# ORPExpansion.net
KiCad netlist of a schematic drawn in EAGLE
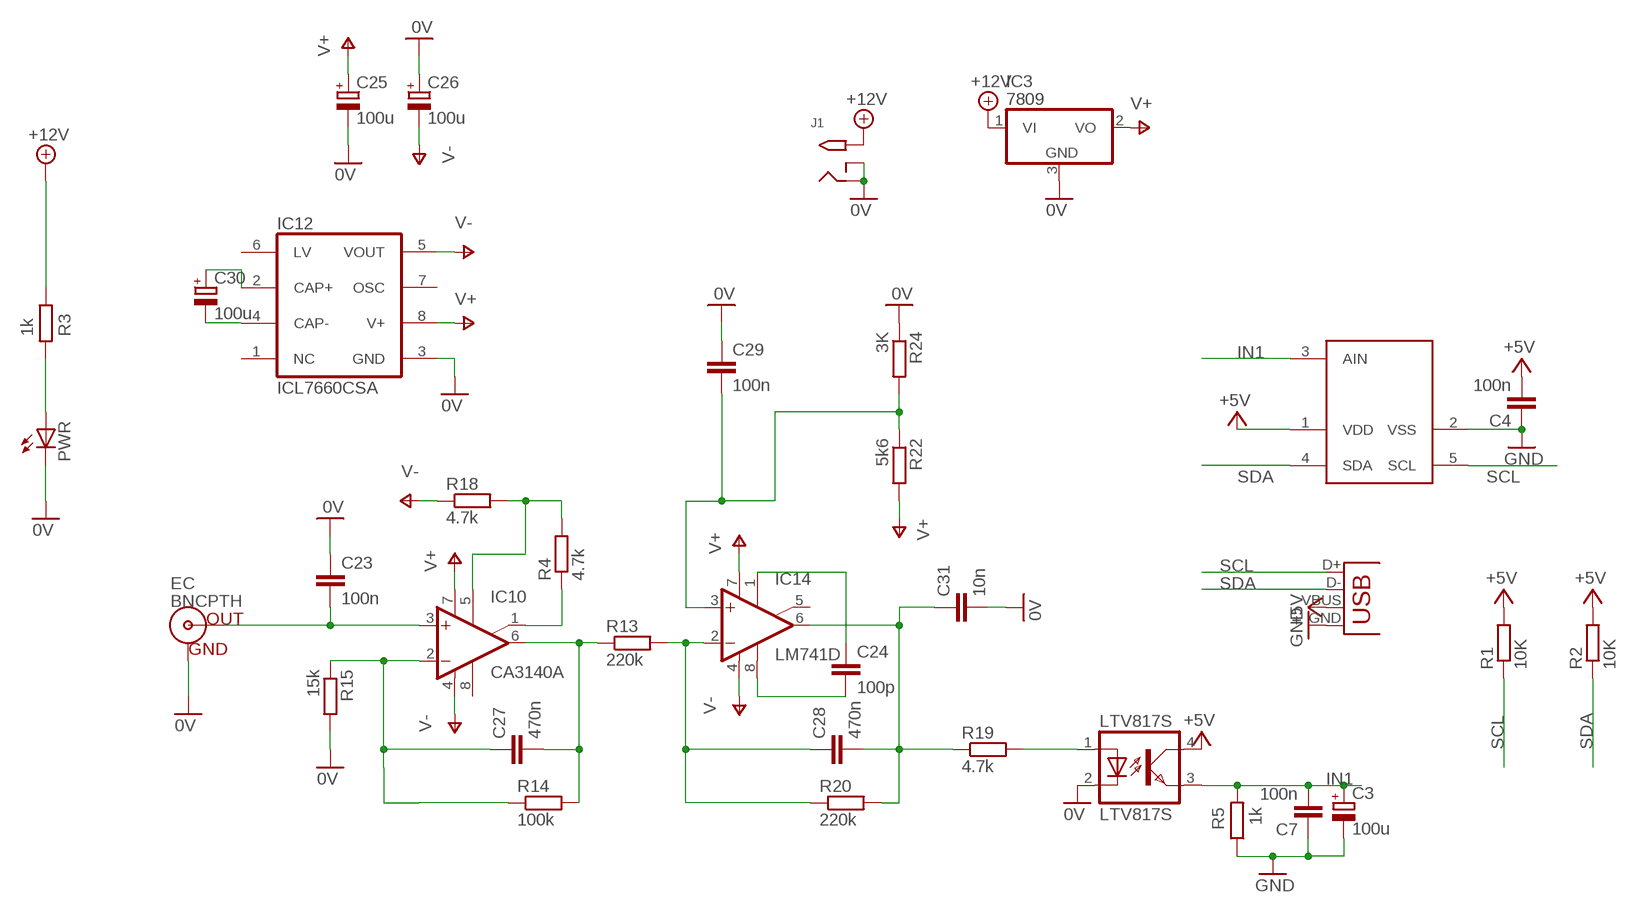
[diagram p0: schematic, sheet 1]

(export (version "E")
  (design (tool "Eeschema 10.0.6"))
  (components
    (comp (ref "C3")
      (value "100u")
      (footprint "eagle-import:PANASONIC_D")
      (libsource (lib "eagle-import") (part "CPOL-EUD"))
    )
    (comp (ref "C4")
      (value "100n")
      (footprint "eagle-import:C0805K")
      (libsource (lib "eagle-import") (part "C-EUC0805K"))
    )
    (comp (ref "C7")
      (value "100n")
      (footprint "eagle-import:C0805K")
      (libsource (lib "eagle-import") (part "C-EUC0805K"))
    )
    (comp (ref "C23")
      (value "100n")
      (footprint "eagle-import:C0805")
      (libsource (lib "eagle-import") (part "C-EUC0805"))
    )
    (comp (ref "C24")
      (value "100p")
      (footprint "eagle-import:C0805")
      (libsource (lib "eagle-import") (part "C-EUC0805"))
    )
    (comp (ref "C25")
      (value "100u")
      (footprint "eagle-import:PANASONIC_D")
      (libsource (lib "eagle-import") (part "CPOL-EUD"))
    )
    (comp (ref "C26")
      (value "100u")
      (footprint "eagle-import:PANASONIC_D")
      (libsource (lib "eagle-import") (part "CPOL-EUD"))
    )
    (comp (ref "C27")
      (value "470n")
      (footprint "eagle-import:C0805")
      (libsource (lib "eagle-import") (part "C-EUC0805"))
    )
    (comp (ref "C28")
      (value "470n")
      (footprint "eagle-import:C0805")
      (libsource (lib "eagle-import") (part "C-EUC0805"))
    )
    (comp (ref "C29")
      (value "100n")
      (footprint "eagle-import:C0805")
      (libsource (lib "eagle-import") (part "C-EUC0805"))
    )
    (comp (ref "C30")
      (value "100u")
      (footprint "eagle-import:PANASONIC_D")
      (libsource (lib "eagle-import") (part "CPOL-EUD"))
    )
    (comp (ref "C31")
      (value "10n")
      (footprint "eagle-import:C0805")
      (libsource (lib "eagle-import") (part "C-EUC0805"))
    )
    (comp (ref "EC")
      (value "BNCPTH")
      (footprint "eagle-import:BNC")
      (libsource (lib "eagle-import") (part "BNCPTH"))
    )
    (comp (ref "IC3")
      (value "7809")
      (footprint "eagle-import:TO252")
      (libsource (lib "eagle-import") (part "78DT05"))
    )
    (comp (ref "IC10")
      (value "CA3140A")
      (footprint "eagle-import:SO08")
      (libsource (lib "eagle-import") (part "CA3140D"))
    )
    (comp (ref "IC12")
      (value "ICL7660CSA")
      (footprint "eagle-import:SO08")
      (libsource (lib "eagle-import") (part "ICL7660CSA"))
    )
    (comp (ref "IC14")
      (value "LM741D")
      (footprint "eagle-import:SO08")
      (libsource (lib "eagle-import") (part "741DLM"))
    )
    (comp (ref "J1")
      (value "2.1MMJACKTHM")
      (footprint "eagle-import:PJ-102A")
      (libsource (lib "eagle-import") (part "2.1MMJACKTHM"))
    )
    (comp (ref "LTV817S")
      (value "LTV817S")
      (footprint "eagle-import:SMD4")
      (libsource (lib "eagle-import") (part "LTV816S"))
    )
    (comp (ref "PWR")
      (value "LED3MM")
      (footprint "eagle-import:LED3MM")
      (libsource (lib "eagle-import") (part "LED3MM"))
    )
    (comp (ref "R1")
      (value "10K")
      (footprint "eagle-import:R0805")
      (libsource (lib "eagle-import") (part "R-EU_R0805"))
    )
    (comp (ref "R2")
      (value "10K")
      (footprint "eagle-import:R0805")
      (libsource (lib "eagle-import") (part "R-EU_R0805"))
    )
    (comp (ref "R3")
      (value "1k")
      (footprint "eagle-import:R0805")
      (libsource (lib "eagle-import") (part "R-EU_R0805"))
    )
    (comp (ref "R4")
      (value "4.7k")
      (footprint "eagle-import:R0805")
      (libsource (lib "eagle-import") (part "R-EU_R0805"))
    )
    (comp (ref "R5")
      (value "1k")
      (footprint "eagle-import:R0805")
      (libsource (lib "eagle-import") (part "R-EU_R0805"))
    )
    (comp (ref "R13")
      (value "220k")
      (footprint "eagle-import:R0805")
      (libsource (lib "eagle-import") (part "R-EU_R0805"))
    )
    (comp (ref "R14")
      (value "100k")
      (footprint "eagle-import:R0805")
      (libsource (lib "eagle-import") (part "R-EU_R0805"))
    )
    (comp (ref "R15")
      (value "15k")
      (footprint "eagle-import:R0805")
      (libsource (lib "eagle-import") (part "R-EU_R0805"))
    )
    (comp (ref "R18")
      (value "4.7k")
      (footprint "eagle-import:R0805")
      (libsource (lib "eagle-import") (part "R-EU_R0805"))
    )
    (comp (ref "R19")
      (value "4.7k")
      (footprint "eagle-import:R0805")
      (libsource (lib "eagle-import") (part "R-EU_R0805"))
    )
    (comp (ref "R20")
      (value "220k")
      (footprint "eagle-import:R0805")
      (libsource (lib "eagle-import") (part "R-EU_R0805"))
    )
    (comp (ref "R22")
      (value "5k6")
      (footprint "eagle-import:R0805")
      (libsource (lib "eagle-import") (part "R-EU_R0805"))
    )
    (comp (ref "R24")
      (value "3K")
      (footprint "eagle-import:R0805")
      (libsource (lib "eagle-import") (part "R-EU_R0805"))
    )
    (comp (ref "U$2")
      (value "MCP3221")
      (footprint "eagle-import:SOT23-5")
      (libsource (lib "eagle-import") (part "MCP3221"))
    )
    (comp (ref "X5")
      (value "USBSMD")
      (footprint "eagle-import:USB-MINIB")
      (libsource (lib "eagle-import") (part "USBSMD"))
    )
  )
  (nets
    (net (code "1") (name "+5V") (class "Default")
      (node (ref "C4") (pin "2") (pinfunction "2_2") (pintype "passive"))
      (node (ref "LTV817S") (pin "4") (pinfunction "COL_4") (pintype "passive"))
      (node (ref "R1") (pin "2") (pinfunction "2_2") (pintype "passive"))
      (node (ref "R2") (pin "2") (pinfunction "2_2") (pintype "passive"))
      (node (ref "U$2") (pin "1") (pinfunction "VDD_1") (pintype "bidirectional"))
      (node (ref "X5") (pin "VBUS") (pinfunction "VBUS_VBUS") (pintype "bidirectional"))
    )
    (net (code "2") (name "+12V") (class "Default")
      (node (ref "IC3") (pin "1") (pinfunction "VI_1") (pintype "input"))
      (node (ref "J1") (pin "TIP") (pinfunction "TIP_TIP") (pintype "bidirectional"))
      (node (ref "R3") (pin "1") (pinfunction "1_1") (pintype "passive"))
    )
    (net (code "3") (name "/IN1") (class "Default")
      (node (ref "C3") (pin "+") (pinfunction "+_+") (pintype "passive"))
      (node (ref "C7") (pin "2") (pinfunction "2_2") (pintype "passive"))
      (node (ref "LTV817S") (pin "3") (pinfunction "EMIT_3") (pintype "passive"))
      (node (ref "R5") (pin "2") (pinfunction "2_2") (pintype "passive"))
      (node (ref "U$2") (pin "3") (pinfunction "AIN_3") (pintype "bidirectional"))
    )
    (net (code "4") (name "/SCL") (class "Default")
      (node (ref "R1") (pin "1") (pinfunction "1_1") (pintype "passive"))
      (node (ref "U$2") (pin "5") (pinfunction "SCL_5") (pintype "bidirectional"))
      (node (ref "X5") (pin "D+") (pinfunction "D+_D+") (pintype "bidirectional"))
    )
    (net (code "5") (name "/SDA") (class "Default")
      (node (ref "R2") (pin "1") (pinfunction "1_1") (pintype "passive"))
      (node (ref "U$2") (pin "4") (pinfunction "SDA_4") (pintype "bidirectional"))
      (node (ref "X5") (pin "D-") (pinfunction "D-_D-") (pintype "bidirectional"))
    )
    (net (code "6") (name "0V") (class "Default")
      (node (ref "C23") (pin "1") (pinfunction "1_1") (pintype "passive"))
      (node (ref "C25") (pin "-") (pinfunction "-_-") (pintype "passive"))
      (node (ref "C26") (pin "+") (pinfunction "+_+") (pintype "passive"))
      (node (ref "C29") (pin "1") (pinfunction "1_1") (pintype "passive"))
      (node (ref "C31") (pin "2") (pinfunction "2_2") (pintype "passive"))
      (node (ref "EC") (pin "GND") (pinfunction "GND_GND") (pintype "bidirectional"))
      (node (ref "IC12") (pin "3") (pinfunction "GND_3") (pintype "power_in"))
      (node (ref "IC3") (pin "3") (pinfunction "GND_3") (pintype "passive"))
      (node (ref "J1") (pin "RING") (pinfunction "RING_RING") (pintype "bidirectional"))
      (node (ref "J1") (pin "RING_SW") (pinfunction "RING_SW_RING_SW") (pintype "bidirectional"))
      (node (ref "LTV817S") (pin "2") (pinfunction "C_2") (pintype "passive"))
      (node (ref "PWR") (pin "K") (pinfunction "C_K") (pintype "passive"))
      (node (ref "R15") (pin "2") (pinfunction "2_2") (pintype "passive"))
      (node (ref "R24") (pin "1") (pinfunction "1_1") (pintype "passive"))
    )
    (net (code "7") (name "GND") (class "Default")
      (node (ref "C3") (pin "-") (pinfunction "-_-") (pintype "passive"))
      (node (ref "C4") (pin "1") (pinfunction "1_1") (pintype "passive"))
      (node (ref "C7") (pin "1") (pinfunction "1_1") (pintype "passive"))
      (node (ref "R5") (pin "1") (pinfunction "1_1") (pintype "passive"))
      (node (ref "U$2") (pin "2") (pinfunction "VSS_2") (pintype "bidirectional"))
      (node (ref "X5") (pin "GND") (pinfunction "GND_GND") (pintype "bidirectional"))
    )
    (net (code "8") (name "Net-(EC-OUT)") (class "Default")
      (node (ref "C23") (pin "2") (pinfunction "2_2") (pintype "passive"))
      (node (ref "EC") (pin "S") (pinfunction "OUT_S") (pintype "bidirectional"))
      (node (ref "IC10") (pin "3") (pinfunction "+IN_3") (pintype "input"))
    )
    (net (code "9") (name "Net-(IC10--IN)") (class "Default")
      (node (ref "C27") (pin "1") (pinfunction "1_1") (pintype "passive"))
      (node (ref "IC10") (pin "2") (pinfunction "-IN_2") (pintype "input"))
      (node (ref "R14") (pin "1") (pinfunction "1_1") (pintype "passive"))
      (node (ref "R15") (pin "1") (pinfunction "1_1") (pintype "passive"))
    )
    (net (code "10") (name "Net-(IC10-ON)") (class "Default")
      (node (ref "IC10") (pin "5") (pinfunction "ON_5") (pintype "passive"))
      (node (ref "R18") (pin "2") (pinfunction "2_2") (pintype "passive"))
      (node (ref "R4") (pin "2") (pinfunction "2_2") (pintype "passive"))
    )
    (net (code "11") (name "Net-(IC10-ON{slash}CMP)") (class "Default")
      (node (ref "IC10") (pin "1") (pinfunction "ON/CMP_1") (pintype "passive"))
      (node (ref "R4") (pin "1") (pinfunction "1_1") (pintype "passive"))
    )
    (net (code "12") (name "Net-(IC10-OUT)") (class "Default")
      (node (ref "C27") (pin "2") (pinfunction "2_2") (pintype "passive"))
      (node (ref "IC10") (pin "6") (pinfunction "OUT_6") (pintype "output"))
      (node (ref "R13") (pin "1") (pinfunction "1_1") (pintype "passive"))
      (node (ref "R14") (pin "2") (pinfunction "2_2") (pintype "passive"))
    )
    (net (code "13") (name "Net-(IC12-CAP+)") (class "Default")
      (node (ref "C30") (pin "+") (pinfunction "+_+") (pintype "passive"))
      (node (ref "IC12") (pin "2") (pinfunction "CAP+_2") (pintype "passive"))
    )
    (net (code "14") (name "Net-(IC12-CAP-)") (class "Default")
      (node (ref "C30") (pin "-") (pinfunction "-_-") (pintype "passive"))
      (node (ref "IC12") (pin "4") (pinfunction "CAP-_4") (pintype "passive"))
    )
    (net (code "15") (name "Net-(IC14-+IN)") (class "Default")
      (node (ref "C29") (pin "2") (pinfunction "2_2") (pintype "passive"))
      (node (ref "IC14") (pin "3") (pinfunction "+IN_3") (pintype "input"))
      (node (ref "R22") (pin "1") (pinfunction "1_1") (pintype "passive"))
      (node (ref "R24") (pin "2") (pinfunction "2_2") (pintype "passive"))
    )
    (net (code "16") (name "Net-(IC14--IN)") (class "Default")
      (node (ref "C28") (pin "1") (pinfunction "1_1") (pintype "passive"))
      (node (ref "IC14") (pin "2") (pinfunction "-IN_2") (pintype "input"))
      (node (ref "R13") (pin "2") (pinfunction "2_2") (pintype "passive"))
      (node (ref "R20") (pin "1") (pinfunction "1_1") (pintype "passive"))
    )
    (net (code "17") (name "Net-(IC14-ON1)") (class "Default")
      (node (ref "C24") (pin "1") (pinfunction "1_1") (pintype "passive"))
      (node (ref "IC14") (pin "1") (pinfunction "ON1_1") (pintype "passive"))
    )
    (net (code "18") (name "Net-(IC14-OPT)") (class "Default")
      (node (ref "C24") (pin "2") (pinfunction "2_2") (pintype "passive"))
      (node (ref "IC14") (pin "8") (pinfunction "OPT_8") (pintype "passive"))
    )
    (net (code "19") (name "Net-(IC14-OUT)") (class "Default")
      (node (ref "C28") (pin "2") (pinfunction "2_2") (pintype "passive"))
      (node (ref "C31") (pin "1") (pinfunction "1_1") (pintype "passive"))
      (node (ref "IC14") (pin "6") (pinfunction "OUT_6") (pintype "output"))
      (node (ref "R19") (pin "1") (pinfunction "1_1") (pintype "passive"))
      (node (ref "R20") (pin "2") (pinfunction "2_2") (pintype "passive"))
    )
    (net (code "20") (name "Net-(LTV817S-A)") (class "Default")
      (node (ref "LTV817S") (pin "1") (pinfunction "A_1") (pintype "passive"))
      (node (ref "R19") (pin "2") (pinfunction "2_2") (pintype "passive"))
    )
    (net (code "21") (name "Net-(PWR-PadA)") (class "Default")
      (node (ref "PWR") (pin "A") (pinfunction "A_A") (pintype "passive"))
      (node (ref "R3") (pin "2") (pinfunction "2_2") (pintype "passive"))
    )
    (net (code "22") (name "V+") (class "Default")
      (node (ref "C25") (pin "+") (pinfunction "+_+") (pintype "passive"))
      (node (ref "IC10") (pin "7") (pinfunction "V+_7") (pintype "power_in"))
      (node (ref "IC12") (pin "8") (pinfunction "V+_8") (pintype "power_in"))
      (node (ref "IC14") (pin "7") (pinfunction "V+_7") (pintype "power_in"))
      (node (ref "IC3") (pin "2") (pinfunction "VO_2") (pintype "passive"))
      (node (ref "R22") (pin "2") (pinfunction "2_2") (pintype "passive"))
    )
    (net (code "23") (name "V-") (class "Default")
      (node (ref "C26") (pin "-") (pinfunction "-_-") (pintype "passive"))
      (node (ref "IC10") (pin "4") (pinfunction "V-_4") (pintype "power_in"))
      (node (ref "IC12") (pin "5") (pinfunction "VOUT_5") (pintype "power_in"))
      (node (ref "IC14") (pin "4") (pinfunction "V-_4") (pintype "power_in"))
      (node (ref "R18") (pin "1") (pinfunction "1_1") (pintype "passive"))
    )
    (net (code "24") (name "unconnected-(IC10-CMP-Pad8)") (class "Default")
      (node (ref "IC10") (pin "8") (pinfunction "CMP_8") (pintype "passive"))
    )
    (net (code "25") (name "unconnected-(IC12-LV-Pad6)") (class "Default")
      (node (ref "IC12") (pin "6") (pinfunction "LV_6") (pintype "passive"))
    )
    (net (code "26") (name "unconnected-(IC12-NC-Pad1)") (class "Default")
      (node (ref "IC12") (pin "1") (pinfunction "NC_1") (pintype "no_connect"))
    )
    (net (code "27") (name "unconnected-(IC12-OSC-Pad7)") (class "Default")
      (node (ref "IC12") (pin "7") (pinfunction "OSC_7") (pintype "output"))
    )
    (net (code "28") (name "unconnected-(IC14-ON2-Pad5)") (class "Default")
      (node (ref "IC14") (pin "5") (pinfunction "ON2_5") (pintype "passive"))
    )
  )
)
